# MCU.net
KiCad netlist of a schematic drawn in Altium Designer
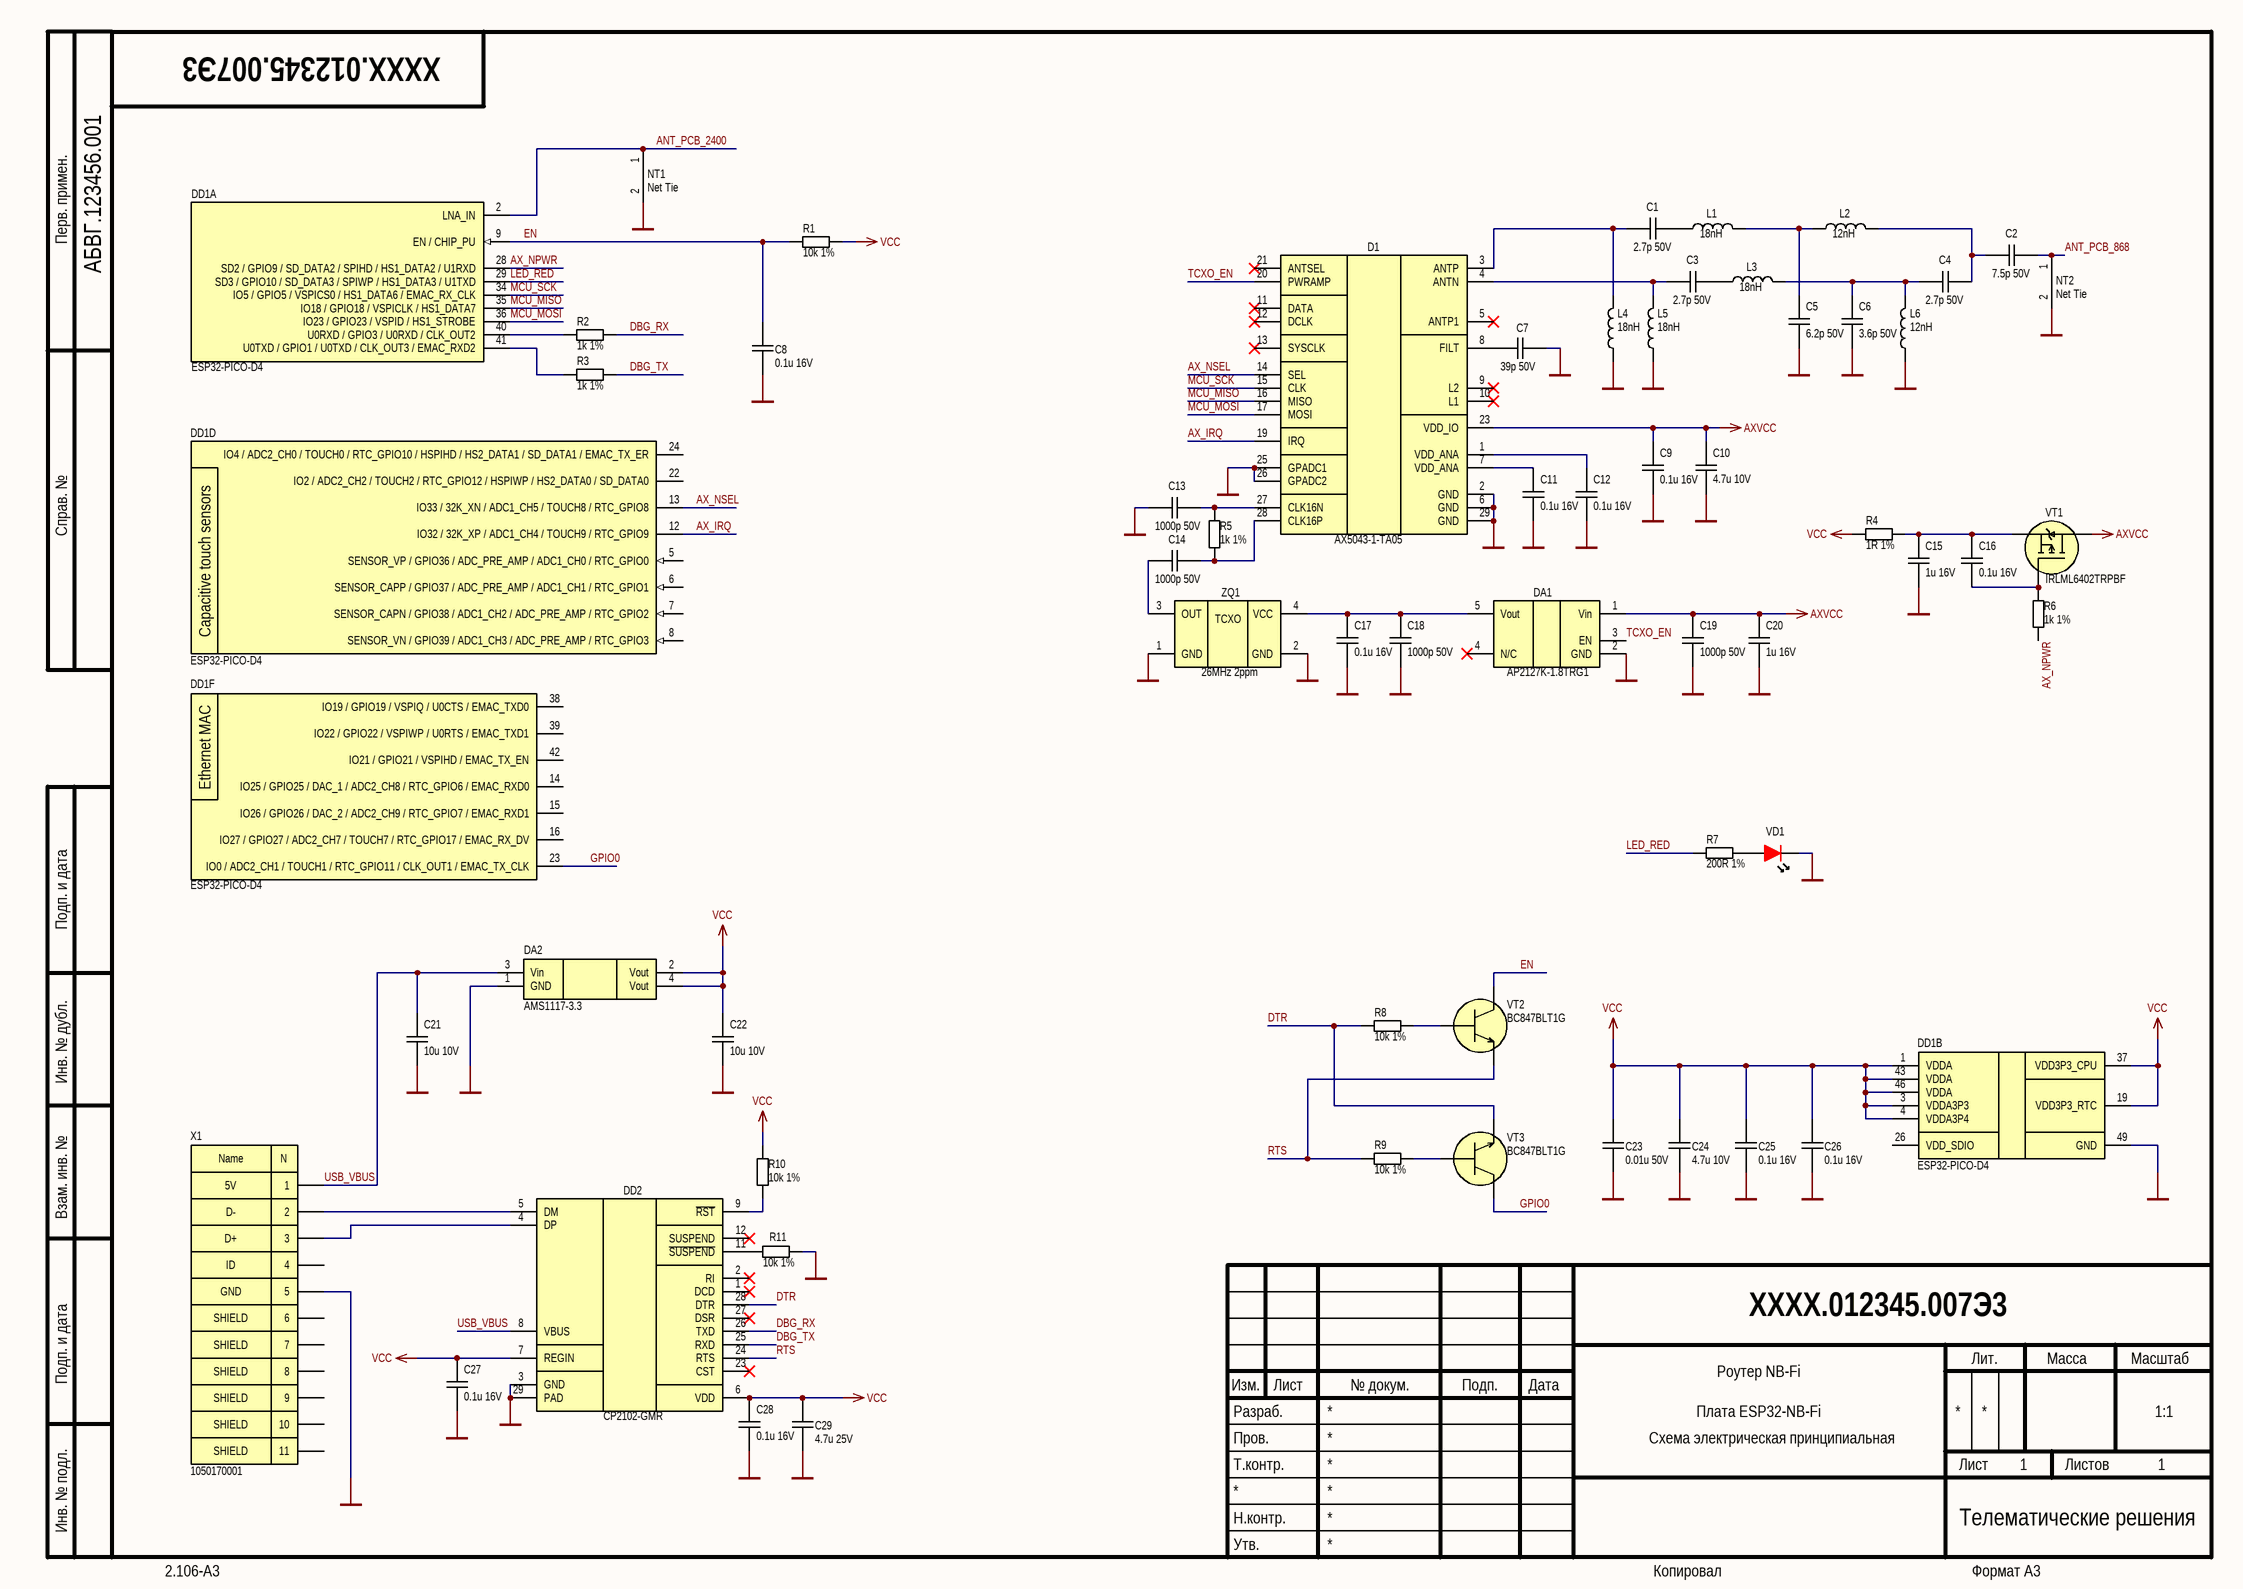
[diagram p0: MCU.SchDoc]

(export (version "E")
  (design (tool "Eeschema 10.0.6"))
  (components
    (comp (ref "C1")
      (value "2.7p 50V")
      (footprint "C0603")
      (description "CERCAP 2.7p/50V 0603 BNPO")
      (fields (field (name "PARTNUMBER") "CC0603BRNPO9BN2R7"))
      (libsource (lib "Capacitors") (part "CC0603BRNPO9BN2R7"))
    )
    (comp (ref "C2")
      (value "7.5p 50V")
      (footprint "C0603")
      (description "CERCAP 7.5p/50V 0603 BNPO")
      (fields (field (name "PARTNUMBER") "CC0603BRNPO9BN7R5"))
      (libsource (lib "Capacitors") (part "CC0603BRNPO9BN7R5"))
    )
    (comp (ref "C3")
      (value "2.7p 50V")
      (footprint "C0603")
      (description "CERCAP 2.7p/50V 0603 BNPO")
      (fields (field (name "PARTNUMBER") "CC0603BRNPO9BN2R7"))
      (libsource (lib "Capacitors") (part "CC0603BRNPO9BN2R7"))
    )
    (comp (ref "C4")
      (value "2.7p 50V")
      (footprint "C0603")
      (description "CERCAP 2.7p/50V 0603 BNPO")
      (fields (field (name "PARTNUMBER") "CC0603BRNPO9BN2R7"))
      (libsource (lib "Capacitors") (part "CC0603BRNPO9BN2R7"))
    )
    (comp (ref "C5")
      (value "6.2p 50V")
      (footprint "C0603")
      (description "CERCAP 6.2p/50V 0603 BNPO")
      (fields (field (name "PARTNUMBER") "CC0603BRNPO9BN6R2"))
      (libsource (lib "Capacitors") (part "CC0603BRNPO9BN6R2"))
    )
    (comp (ref "C6")
      (value "3.6p 50V")
      (footprint "C0603")
      (description "CERCAP 3.6p/50V 0603 BNPO")
      (fields (field (name "PARTNUMBER") "CC0603BRNPO9BN3R6"))
      (libsource (lib "Capacitors") (part "CC0603BRNPO9BN3R6"))
    )
    (comp (ref "C7")
      (value "39p 50V")
      (footprint "C0603")
      (description "CERCAP 39p/50V 0603 JNPO")
      (fields (field (name "PARTNUMBER") "CC0603JRNPO9BN390"))
      (libsource (lib "Capacitors") (part "CC0603JRNPO9BN390"))
    )
    (comp (ref "C8")
      (value "0.1u 16V")
      (footprint "C0603")
      (description "CERCAP 0.1/16V 0603 KX7R")
      (fields (field (name "PARTNUMBER") "CC0603KRX7R7BB104"))
      (libsource (lib "Capacitors") (part "CC0603KRX7R7BB104"))
    )
    (comp (ref "C9")
      (value "0.1u 16V")
      (footprint "C0603")
      (description "CERCAP 0.1/16V 0603 KX7R")
      (fields (field (name "PARTNUMBER") "CC0603KRX7R7BB104"))
      (libsource (lib "Capacitors") (part "CC0603KRX7R7BB104"))
    )
    (comp (ref "C10")
      (value "4.7u 10V")
      (footprint "C0603")
      (description "CERCAP 4.7/10V 0603 KX5R")
      (fields (field (name "PARTNUMBER") "CC0603KRX5R6BB475"))
      (libsource (lib "Passive") (part "C"))
    )
    (comp (ref "C11")
      (value "0.1u 16V")
      (footprint "C0603")
      (description "CERCAP 0.1/16V 0603 KX7R")
      (fields (field (name "PARTNUMBER") "CC0603KRX7R7BB104"))
      (libsource (lib "Capacitors") (part "CC0603KRX7R7BB104"))
    )
    (comp (ref "C12")
      (value "0.1u 16V")
      (footprint "C0603")
      (description "CERCAP 0.1/16V 0603 KX7R")
      (fields (field (name "PARTNUMBER") "CC0603KRX7R7BB104"))
      (libsource (lib "Capacitors") (part "CC0603KRX7R7BB104"))
    )
    (comp (ref "C13")
      (value "1000p 50V")
      (footprint "C0603")
      (description "CERCAP 1000p/50V 0603 JNPO")
      (fields (field (name "PARTNUMBER") "CC0603JRNPO9BN102"))
      (libsource (lib "Capacitors") (part "CC0603JRNPO9BN102"))
    )
    (comp (ref "C14")
      (value "1000p 50V")
      (footprint "C0603")
      (description "CERCAP 1000p/50V 0603 JNPO")
      (fields (field (name "PARTNUMBER") "CC0603JRNPO9BN102"))
      (libsource (lib "Capacitors") (part "CC0603JRNPO9BN102"))
    )
    (comp (ref "C15")
      (value "1u 16V")
      (footprint "C0603")
      (description "CERCAP 1/16V 0603 KX7R")
      (fields (field (name "PARTNUMBER") "CC0603KRX7R7BB105"))
      (libsource (lib "Capacitors") (part "CC0603KRX7R7BB105"))
    )
    (comp (ref "C16")
      (value "0.1u 16V")
      (footprint "C0603")
      (description "CERCAP 0.1/16V 0603 KX7R")
      (fields (field (name "PARTNUMBER") "CC0603KRX7R7BB104"))
      (libsource (lib "Capacitors") (part "CC0603KRX7R7BB104"))
    )
    (comp (ref "C17")
      (value "0.1u 16V")
      (footprint "C0603")
      (description "CERCAP 0.1/16V 0603 KX7R")
      (fields (field (name "PARTNUMBER") "CC0603KRX7R7BB104"))
      (libsource (lib "Capacitors") (part "CC0603KRX7R7BB104"))
    )
    (comp (ref "C18")
      (value "1000p 50V")
      (footprint "C0603")
      (description "CERCAP 1000p/50V 0603 JNPO")
      (fields (field (name "PARTNUMBER") "CC0603JRNPO9BN102"))
      (libsource (lib "Capacitors") (part "CC0603JRNPO9BN102"))
    )
    (comp (ref "C19")
      (value "1000p 50V")
      (footprint "C0603")
      (description "CERCAP 1000p/50V 0603 JNPO")
      (fields (field (name "PARTNUMBER") "CC0603JRNPO9BN102"))
      (libsource (lib "Capacitors") (part "CC0603JRNPO9BN102"))
    )
    (comp (ref "C20")
      (value "1u 16V")
      (footprint "C0603")
      (description "CERCAP 1/16V 0603 KX7R")
      (fields (field (name "PARTNUMBER") "CC0603KRX7R7BB105"))
      (libsource (lib "Capacitors") (part "CC0603KRX7R7BB105"))
    )
    (comp (ref "C21")
      (value "10u 10V")
      (footprint "C0805")
      (description "10µF ±10% 10V Ceramic Capacitor X5R 0805 (2012 Metric)")
      (fields (field (name "PARTNUMBER") "CL21A106KPFNNNG"))
      (libsource (lib "Capacitors") (part "CL21A106KPFNNNG"))
    )
    (comp (ref "C22")
      (value "10u 10V")
      (footprint "C0805")
      (description "10µF ±10% 10V Ceramic Capacitor X5R 0805 (2012 Metric)")
      (fields (field (name "PARTNUMBER") "CL21A106KPFNNNG"))
      (libsource (lib "Capacitors") (part "CL21A106KPFNNNG"))
    )
    (comp (ref "C23")
      (value "0.01u 50V")
      (footprint "C0603")
      (description "CAP CER 10000PF 50V X7R 0603")
      (fields (field (name "PARTNUMBER") "CC0603KRX7R9BB103"))
      (libsource (lib "Capacitors") (part "CC0603KRX7R9BB103"))
    )
    (comp (ref "C24")
      (value "4.7u 10V")
      (footprint "C0603")
      (description "CERCAP 4.7/10V 0603 KX5R")
      (fields (field (name "PARTNUMBER") "CC0603KRX5R6BB475"))
      (libsource (lib "Passive") (part "C"))
    )
    (comp (ref "C25")
      (value "0.1u 16V")
      (footprint "C0603")
      (description "CERCAP 0.1/16V 0603 KX7R")
      (fields (field (name "PARTNUMBER") "CC0603KRX7R7BB104"))
      (libsource (lib "Capacitors") (part "CC0603KRX7R7BB104"))
    )
    (comp (ref "C26")
      (value "0.1u 16V")
      (footprint "C0603")
      (description "CERCAP 0.1/16V 0603 KX7R")
      (fields (field (name "PARTNUMBER") "CC0603KRX7R7BB104"))
      (libsource (lib "Capacitors") (part "CC0603KRX7R7BB104"))
    )
    (comp (ref "C27")
      (value "0.1u 16V")
      (footprint "C0603")
      (description "CERCAP 0.1/16V 0603 KX7R")
      (fields (field (name "PARTNUMBER") "CC0603KRX7R7BB104"))
      (libsource (lib "Capacitors") (part "CC0603KRX7R7BB104"))
    )
    (comp (ref "C28")
      (value "0.1u 16V")
      (footprint "C0603")
      (description "CERCAP 0.1/16V 0603 KX7R")
      (fields (field (name "PARTNUMBER") "CC0603KRX7R7BB104"))
      (libsource (lib "Capacitors") (part "CC0603KRX7R7BB104"))
    )
    (comp (ref "C29")
      (value "4.7u 25V")
      (footprint "C0805")
      (description "4.7µF ±10% 25V Ceramic Capacitor X5R 0805 (2012 Metric)")
      (fields (field (name "PARTNUMBER") "CL21A475KAQNNNE"))
      (libsource (lib "Capacitors") (part "CL21A475KAQNNNE"))
    )
    (comp (ref "D1")
      (value "AX5043-1-TA05")
      (footprint "QFN28")
      (description "RF Transceiver RADIO TRANSCEIVER")
      (libsource (lib "Integrated Circuits (ICs)") (part "AX5043-1-TA05"))
    )
    (comp (ref "DA1")
      (value "AP2127K-1.8TRG1")
      (footprint "SOT23-5")
      (description "LDO Voltage Regulators 1.8V 80mA CMOS LDO w/Enable")
      (libsource (lib "Integrated Circuits (ICs)") (part "AP2127K-1.8TRG1"))
    )
    (comp (ref "DA2")
      (value "AMS1117-3.3")
      (footprint "SOT223-4")
      (description "1A LOW DROPOUT VOLTAGE REGULATOR")
      (libsource (lib "Integrated Circuits (ICs)") (part "AMS1117-3.3"))
    )
    (comp (ref "DD1")
      (value "ESP32-PICO-D4")
      (footprint "QFN48-7x7")
      (libsource (lib "Integrated Circuits (ICs)") (part "ESP32-PICO-D4"))
    )
    (comp (ref "DD2")
      (value "CP2102-GMR")
      (footprint "QFN28")
      (description "IC USB-TO-UART BRIDGE 28VQFN")
      (libsource (lib "Integrated Circuits (ICs)") (part "CP2102-GMR"))
    )
    (comp (ref "L1")
      (value "18nH")
      (footprint "L0603_LQW")
      (description "Fixed Inductors 0603 18nH 2%")
      (fields (field (name "PARTNUMBER") "LQW18AN18NG00D"))
      (libsource (lib "Inductors") (part "LQW18AN18NG00D"))
    )
    (comp (ref "L2")
      (value "12nH")
      (footprint "L0603_LQW")
      (description "Fixed Inductors 12 NH 5% (R)")
      (fields (field (name "PARTNUMBER") "LQW18AN12NJ00D"))
      (libsource (lib "Inductors") (part "LQW18AN12NJ00D"))
    )
    (comp (ref "L3")
      (value "18nH")
      (footprint "L0603_LQW")
      (description "Fixed Inductors 0603 18nH 2%")
      (fields (field (name "PARTNUMBER") "LQW18AN18NG00D"))
      (libsource (lib "Inductors") (part "LQW18AN18NG00D"))
    )
    (comp (ref "L4")
      (value "18nH")
      (footprint "L0603_LQW")
      (description "Fixed Inductors 0603 18nH 2%")
      (fields (field (name "PARTNUMBER") "LQW18AN18NG00D"))
      (libsource (lib "Inductors") (part "LQW18AN18NG00D"))
    )
    (comp (ref "L5")
      (value "18nH")
      (footprint "L0603_LQW")
      (description "Fixed Inductors 0603 18nH 2%")
      (fields (field (name "PARTNUMBER") "LQW18AN18NG00D"))
      (libsource (lib "Inductors") (part "LQW18AN18NG00D"))
    )
    (comp (ref "L6")
      (value "12nH")
      (description "Fixed Inductors 12 NH 5% (R)")
      (fields (field (name "PARTNUMBER") "LQW18AN12NJ00D"))
      (libsource (lib "Inductors") (part "LQW18AN12NJ00D"))
    )
    (comp (ref "NT1")
      (value "Net Tie")
      (footprint "NETTIE-5.0x2.0")
      (description "PCB Net Tie")
      (libsource (lib "Special") (part "NT-1"))
    )
    (comp (ref "NT2")
      (value "Net Tie")
      (footprint "NETTIE-5.0x2.0")
      (description "PCB Net Tie")
      (libsource (lib "Special") (part "NT-1"))
    )
    (comp (ref "R1")
      (value "10k 1%")
      (footprint "R0603")
      (description "RES 0603 10K 1%")
      (fields (field (name "PARTNUMBER") "RC0603FR-0710KL"))
      (libsource (lib "") (part "RC0603FR-0710KL_1"))
    )
    (comp (ref "R2")
      (value "1k 1%")
      (footprint "R0603")
      (description "RES 0603 1K 1%")
      (fields (field (name "PARTNUMBER") "RC0603FR-071KL"))
      (libsource (lib "Resistors") (part "RC0603FR-071KL"))
    )
    (comp (ref "R3")
      (value "1k 1%")
      (footprint "R0603")
      (description "RES 0603 1K 1%")
      (fields (field (name "PARTNUMBER") "RC0603FR-071KL"))
      (libsource (lib "Resistors") (part "RC0603FR-071KL"))
    )
    (comp (ref "R4")
      (value "1R 1%")
      (footprint "R0603")
      (description "RES 0603 1R 1%")
      (fields (field (name "PARTNUMBER") "RC0603FR-071RL"))
      (libsource (lib "Passive") (part "R"))
    )
    (comp (ref "R5")
      (value "1k 1%")
      (footprint "R0603")
      (description "RES 0603 1K 1%")
      (fields (field (name "PARTNUMBER") "RC0603FR-071KL"))
      (libsource (lib "Resistors") (part "RC0603FR-071KL"))
    )
    (comp (ref "R6")
      (value "1k 1%")
      (footprint "R0603")
      (description "RES 0603 1K 1%")
      (fields (field (name "PARTNUMBER") "RC0603FR-071KL"))
      (libsource (lib "Resistors") (part "RC0603FR-071KL"))
    )
    (comp (ref "R7")
      (value "200R 1%")
      (footprint "R0603")
      (description "RES 0603 200R 1%")
      (fields (field (name "PARTNUMBER") "RC0603FR-07200RL"))
      (libsource (lib "Resistors") (part "RC0603FR-07200RL"))
    )
    (comp (ref "R8")
      (value "10k 1%")
      (footprint "R0603")
      (description "RES 0603 10K 1%")
      (fields (field (name "PARTNUMBER") "RC0603FR-0710KL"))
      (libsource (lib "") (part "RC0603FR-0710KL_1"))
    )
    (comp (ref "R9")
      (value "10k 1%")
      (footprint "R0603")
      (description "RES 0603 10K 1%")
      (fields (field (name "PARTNUMBER") "RC0603FR-0710KL"))
      (libsource (lib "") (part "RC0603FR-0710KL_1"))
    )
    (comp (ref "R10")
      (value "10k 1%")
      (footprint "R0603")
      (description "RES 0603 10K 1%")
      (fields (field (name "PARTNUMBER") "RC0603FR-0710KL"))
      (libsource (lib "Resistors") (part "RC0603FR-0710KL"))
    )
    (comp (ref "R11")
      (value "10k 1%")
      (footprint "R0603")
      (description "RES 0603 10K 1%")
      (fields (field (name "PARTNUMBER") "RC0603FR-0710KL"))
      (libsource (lib "") (part "RC0603FR-0710KL_2"))
    )
    (comp (ref "VD1")
      (value "RED")
      (footprint "LED0603_RED")
      (description "LED Red 0603")
      (fields (field (name "PARTNUMBER") "FYLS-0603URC"))
      (libsource (lib "Diodes") (part "FYLS-0603URC"))
    )
    (comp (ref "VT1")
      (value "IRLML6402TRPBF")
      (footprint "SOT23-3L")
      (description "MOSFET MOSFT P-Ch -3.7A 65mOhm 8nC Log Lvl")
      (libsource (lib "Discrete Semiconductor Products") (part "IRLML6402TRPBF"))
    )
    (comp (ref "VT2")
      (value "BC847BLT1G")
      (footprint "SOT23-3L")
      (description "Bipolar (BJT) Transistor NPN 45V 100mA 100MHz 300mW Surface Mount SOT-23-3 (TO-236)")
      (libsource (lib "Discrete Semiconductor Products") (part "BC847BLT1G"))
    )
    (comp (ref "VT3")
      (value "BC847BLT1G")
      (footprint "SOT23-3L")
      (description "Bipolar (BJT) Transistor NPN 45V 100mA 100MHz 300mW Surface Mount SOT-23-3 (TO-236)")
      (libsource (lib "Discrete Semiconductor Products") (part "BC847BLT1G"))
    )
    (comp (ref "X1")
      (value "1050170001")
      (footprint "1050170001")
      (description "USB - micro B USB 2.0 Receptacle Connector 5 Position Surface Mount, Right Angle; Through Hole")
      (libsource (lib "Connectors") (part "1050170001"))
    )
    (comp (ref "ZQ1")
      (value "26MHz 2ppm")
      (footprint "QSMD2.0x1.6x0.7")
      (description "TCXO Oscillator 4-pin")
      (fields (field (name "PARTNUMBER") "NT2016SA-26.000000MHZ-NBG2"))
      (libsource (lib "Crystals, Oscillators, Resonators") (part "NT2016SA-26.000000MHZ-NBG2"))
    )
  )
  (nets
    (net (code "1") (name "/ANT_PCB_868") (class "Default")
      (node (ref "C2") (pin "2") (pinfunction "2_2") (pintype "passive"))
      (node (ref "NT2") (pin "1") (pinfunction "1_1") (pintype "passive"))
    )
    (net (code "2") (name "/ANT_PCB_2400") (class "Default")
      (node (ref "DD1") (pin "2") (pinfunction "LNA_IN_2") (pintype "passive"))
      (node (ref "NT1") (pin "1") (pinfunction "1_1") (pintype "passive"))
    )
    (net (code "3") (name "/AX_IRQ") (class "Default")
      (node (ref "D1") (pin "19") (pinfunction "IRQ_19") (pintype "passive"))
      (node (ref "DD1") (pin "12") (pinfunction "IO32_/_32K_XP_/_ADC1_CH4_/_TOUCH9_/_RTC_GPIO9_12") (pintype "passive"))
    )
    (net (code "4") (name "/AX_NPWR") (class "Default")
      (node (ref "DD1") (pin "28") (pinfunction "SD2_/_GPIO9_/_SD_DATA2_/_SPIHD_/_HS1_DATA2_/_U1RXD_28") (pintype "passive"))
      (node (ref "R6") (pin "1") (pinfunction "1_1") (pintype "passive"))
    )
    (net (code "5") (name "/AX_NSEL") (class "Default")
      (node (ref "D1") (pin "14") (pinfunction "SEL_14") (pintype "passive"))
      (node (ref "DD1") (pin "13") (pinfunction "IO33_/_32K_XN_/_ADC1_CH5_/_TOUCH8_/_RTC_GPIO8_13") (pintype "passive"))
    )
    (net (code "6") (name "/DBG_RX") (class "Default")
      (node (ref "DD2") (pin "26") (pinfunction "TXD_26") (pintype "passive"))
      (node (ref "R2") (pin "2") (pinfunction "2_2") (pintype "passive"))
    )
    (net (code "7") (name "/DBG_TX") (class "Default")
      (node (ref "DD2") (pin "25") (pinfunction "RXD_25") (pintype "passive"))
      (node (ref "R3") (pin "2") (pinfunction "2_2") (pintype "passive"))
    )
    (net (code "8") (name "/DTR") (class "Default")
      (node (ref "DD2") (pin "28") (pinfunction "DTR_28") (pintype "passive"))
      (node (ref "R8") (pin "1") (pinfunction "1_1") (pintype "passive"))
      (node (ref "VT3") (pin "2") (pinfunction "E_2") (pintype "passive"))
    )
    (net (code "9") (name "/EN") (class "Default")
      (node (ref "C8") (pin "2") (pinfunction "2_2") (pintype "passive"))
      (node (ref "DD1") (pin "9") (pinfunction "EN_/_CHIP_PU_9") (pintype "input"))
      (node (ref "R1") (pin "1") (pinfunction "1_1") (pintype "passive"))
      (node (ref "VT2") (pin "3") (pinfunction "C_3") (pintype "passive"))
    )
    (net (code "10") (name "/GPIO0") (class "Default")
      (node (ref "DD1") (pin "23") (pinfunction "IO0_/_ADC2_CH1_/_TOUCH1_/_RTC_GPIO11_/_CLK_OUT1_/_EMAC_TX_CLK_23") (pintype "passive"))
      (node (ref "VT3") (pin "3") (pinfunction "C_3") (pintype "passive"))
    )
    (net (code "11") (name "/LED_RED") (class "Default")
      (node (ref "DD1") (pin "29") (pinfunction "SD3_/_GPIO10_/_SD_DATA3_/_SPIWP_/_HS1_DATA3_/_U1TXD_29") (pintype "open_collector"))
      (node (ref "R7") (pin "1") (pinfunction "1_1") (pintype "passive"))
    )
    (net (code "12") (name "/MCU_MISO") (class "Default")
      (node (ref "D1") (pin "16") (pinfunction "MISO_16") (pintype "passive"))
      (node (ref "DD1") (pin "35") (pinfunction "IO18_/_GPIO18_/_VSPICLK_/_HS1_DATA7_35") (pintype "open_collector"))
    )
    (net (code "13") (name "/MCU_MOSI") (class "Default")
      (node (ref "D1") (pin "17") (pinfunction "MOSI_17") (pintype "passive"))
      (node (ref "DD1") (pin "36") (pinfunction "IO23_/_GPIO23_/_VSPID_/_HS1_STROBE_36") (pintype "passive"))
    )
    (net (code "14") (name "/MCU_SCK") (class "Default")
      (node (ref "D1") (pin "15") (pinfunction "CLK_15") (pintype "passive"))
      (node (ref "DD1") (pin "34") (pinfunction "IO5_/_GPIO5_/_VSPICS0_/_HS1_DATA6_/_EMAC_RX_CLK_34") (pintype "passive"))
    )
    (net (code "15") (name "/RTS") (class "Default")
      (node (ref "DD2") (pin "24") (pinfunction "RTS_24") (pintype "passive"))
      (node (ref "R9") (pin "1") (pinfunction "1_1") (pintype "passive"))
      (node (ref "VT2") (pin "2") (pinfunction "E_2") (pintype "passive"))
    )
    (net (code "16") (name "/TCXO_EN") (class "Default")
      (node (ref "D1") (pin "20") (pinfunction "PWRAMP_20") (pintype "passive"))
      (node (ref "DA1") (pin "3") (pinfunction "EN_3") (pintype "passive"))
    )
    (net (code "17") (name "/USB_VBUS") (class "Default")
      (node (ref "C21") (pin "2") (pinfunction "2_2") (pintype "passive"))
      (node (ref "DA2") (pin "3") (pinfunction "Vin_3") (pintype "passive"))
      (node (ref "DD2") (pin "8") (pinfunction "VBUS_8") (pintype "passive"))
      (node (ref "X1") (pin "1") (pinfunction "1_1") (pintype "passive"))
    )
    (net (code "18") (name "AXVCC") (class "Default")
      (node (ref "C10") (pin "2") (pinfunction "2_2") (pintype "passive"))
      (node (ref "C19") (pin "1") (pinfunction "1_1") (pintype "passive"))
      (node (ref "C20") (pin "2") (pinfunction "2_2") (pintype "passive"))
      (node (ref "C9") (pin "2") (pinfunction "2_2") (pintype "passive"))
      (node (ref "D1") (pin "23") (pinfunction "VDD_IO_23") (pintype "passive"))
      (node (ref "DA1") (pin "1") (pinfunction "Vin_1") (pintype "passive"))
      (node (ref "VT1") (pin "3") (pinfunction "D_3") (pintype "passive"))
    )
    (net (code "19") (name "GND") (class "Default")
      (node (ref "C10") (pin "1") (pinfunction "1_1") (pintype "passive"))
      (node (ref "C11") (pin "1") (pinfunction "1_1") (pintype "passive"))
      (node (ref "C12") (pin "1") (pinfunction "1_1") (pintype "passive"))
      (node (ref "C13") (pin "2") (pinfunction "2_2") (pintype "passive"))
      (node (ref "C15") (pin "1") (pinfunction "1_1") (pintype "passive"))
      (node (ref "C17") (pin "1") (pinfunction "1_1") (pintype "passive"))
      (node (ref "C18") (pin "2") (pinfunction "2_2") (pintype "passive"))
      (node (ref "C19") (pin "2") (pinfunction "2_2") (pintype "passive"))
      (node (ref "C20") (pin "1") (pinfunction "1_1") (pintype "passive"))
      (node (ref "C21") (pin "1") (pinfunction "1_1") (pintype "passive"))
      (node (ref "C22") (pin "1") (pinfunction "1_1") (pintype "passive"))
      (node (ref "C23") (pin "1") (pinfunction "1_1") (pintype "passive"))
      (node (ref "C24") (pin "1") (pinfunction "1_1") (pintype "passive"))
      (node (ref "C25") (pin "1") (pinfunction "1_1") (pintype "passive"))
      (node (ref "C26") (pin "1") (pinfunction "1_1") (pintype "passive"))
      (node (ref "C27") (pin "1") (pinfunction "1_1") (pintype "passive"))
      (node (ref "C28") (pin "1") (pinfunction "1_1") (pintype "passive"))
      (node (ref "C29") (pin "1") (pinfunction "1_1") (pintype "passive"))
      (node (ref "C5") (pin "1") (pinfunction "1_1") (pintype "passive"))
      (node (ref "C6") (pin "1") (pinfunction "1_1") (pintype "passive"))
      (node (ref "C7") (pin "2") (pinfunction "2_2") (pintype "passive"))
      (node (ref "C8") (pin "1") (pinfunction "1_1") (pintype "passive"))
      (node (ref "C9") (pin "1") (pinfunction "1_1") (pintype "passive"))
      (node (ref "D1") (pin "2") (pinfunction "GND_2") (pintype "passive"))
      (node (ref "D1") (pin "25") (pinfunction "GPADC1_25") (pintype "passive"))
      (node (ref "D1") (pin "26") (pinfunction "GPADC2_26") (pintype "passive"))
      (node (ref "D1") (pin "29") (pinfunction "GND_29") (pintype "passive"))
      (node (ref "D1") (pin "6") (pinfunction "GND_6") (pintype "passive"))
      (node (ref "DA1") (pin "2") (pinfunction "GND_2") (pintype "passive"))
      (node (ref "DA2") (pin "1") (pinfunction "GND_1") (pintype "passive"))
      (node (ref "DD1") (pin "49") (pinfunction "GND_49") (pintype "power_in"))
      (node (ref "DD2") (pin "29") (pinfunction "PAD_29") (pintype "passive"))
      (node (ref "DD2") (pin "3") (pinfunction "GND_3") (pintype "passive"))
      (node (ref "L4") (pin "1") (pinfunction "1_1") (pintype "passive"))
      (node (ref "L5") (pin "1") (pinfunction "1_1") (pintype "passive"))
      (node (ref "L6") (pin "1") (pinfunction "1_1") (pintype "passive"))
      (node (ref "NT1") (pin "2") (pinfunction "2_2") (pintype "passive"))
      (node (ref "NT2") (pin "2") (pinfunction "2_2") (pintype "passive"))
      (node (ref "R11") (pin "1") (pinfunction "1_1") (pintype "passive"))
      (node (ref "VD1") (pin "2") (pinfunction "2_2") (pintype "passive"))
      (node (ref "X1") (pin "5") (pinfunction "5_5") (pintype "passive"))
      (node (ref "ZQ1") (pin "1") (pinfunction "GND_1") (pintype "passive"))
      (node (ref "ZQ1") (pin "2") (pinfunction "GND_2") (pintype "passive"))
    )
    (net (code "20") (name "Net-(C1-Pad2)") (class "Default")
      (node (ref "C1") (pin "2") (pinfunction "2_2") (pintype "passive"))
      (node (ref "L1") (pin "1") (pinfunction "1_1") (pintype "passive"))
    )
    (net (code "21") (name "Net-(C2-Pad1)") (class "Default")
      (node (ref "C2") (pin "1") (pinfunction "1_1") (pintype "passive"))
      (node (ref "C4") (pin "2") (pinfunction "2_2") (pintype "passive"))
      (node (ref "L2") (pin "2") (pinfunction "2_2") (pintype "passive"))
    )
    (net (code "22") (name "Net-(C3-Pad2)") (class "Default")
      (node (ref "C3") (pin "2") (pinfunction "2_2") (pintype "passive"))
      (node (ref "L3") (pin "1") (pinfunction "1_1") (pintype "passive"))
    )
    (net (code "23") (name "Net-(C4-Pad1)") (class "Default")
      (node (ref "C4") (pin "1") (pinfunction "1_1") (pintype "passive"))
      (node (ref "C6") (pin "2") (pinfunction "2_2") (pintype "passive"))
      (node (ref "L3") (pin "2") (pinfunction "2_2") (pintype "passive"))
      (node (ref "L6") (pin "2") (pinfunction "2_2") (pintype "passive"))
    )
    (net (code "24") (name "Net-(C5-Pad2)") (class "Default")
      (node (ref "C5") (pin "2") (pinfunction "2_2") (pintype "passive"))
      (node (ref "L1") (pin "2") (pinfunction "2_2") (pintype "passive"))
      (node (ref "L2") (pin "1") (pinfunction "1_1") (pintype "passive"))
    )
    (net (code "25") (name "Net-(C11-Pad2)") (class "Default")
      (node (ref "C11") (pin "2") (pinfunction "2_2") (pintype "passive"))
      (node (ref "D1") (pin "7") (pinfunction "VDD_ANA_7") (pintype "passive"))
    )
    (net (code "26") (name "Net-(C12-Pad2)") (class "Default")
      (node (ref "C12") (pin "2") (pinfunction "2_2") (pintype "passive"))
      (node (ref "D1") (pin "1") (pinfunction "VDD_ANA_1") (pintype "passive"))
    )
    (net (code "27") (name "Net-(D1-ANTN)") (class "Default")
      (node (ref "C3") (pin "1") (pinfunction "1_1") (pintype "passive"))
      (node (ref "D1") (pin "4") (pinfunction "ANTN_4") (pintype "passive"))
      (node (ref "L5") (pin "2") (pinfunction "2_2") (pintype "passive"))
    )
    (net (code "28") (name "Net-(D1-ANTP)") (class "Default")
      (node (ref "C1") (pin "1") (pinfunction "1_1") (pintype "passive"))
      (node (ref "D1") (pin "3") (pinfunction "ANTP_3") (pintype "passive"))
      (node (ref "L4") (pin "2") (pinfunction "2_2") (pintype "passive"))
    )
    (net (code "29") (name "Net-(D1-CLK16N)") (class "Default")
      (node (ref "C13") (pin "1") (pinfunction "1_1") (pintype "passive"))
      (node (ref "D1") (pin "27") (pinfunction "CLK16N_27") (pintype "passive"))
      (node (ref "R5") (pin "2") (pinfunction "2_2") (pintype "passive"))
    )
    (net (code "30") (name "Net-(D1-CLK16P)") (class "Default")
      (node (ref "C14") (pin "1") (pinfunction "1_1") (pintype "passive"))
      (node (ref "D1") (pin "28") (pinfunction "CLK16P_28") (pintype "passive"))
      (node (ref "R5") (pin "1") (pinfunction "1_1") (pintype "passive"))
    )
    (net (code "31") (name "Net-(D1-FILT)") (class "Default")
      (node (ref "C7") (pin "1") (pinfunction "1_1") (pintype "passive"))
      (node (ref "D1") (pin "8") (pinfunction "FILT_8") (pintype "passive"))
    )
    (net (code "32") (name "Net-(DA1-Vout)") (class "Default")
      (node (ref "C17") (pin "2") (pinfunction "2_2") (pintype "passive"))
      (node (ref "C18") (pin "1") (pinfunction "1_1") (pintype "passive"))
      (node (ref "DA1") (pin "5") (pinfunction "Vout_5") (pintype "passive"))
      (node (ref "ZQ1") (pin "4") (pinfunction "VCC_4") (pintype "passive"))
    )
    (net (code "33") (name "Net-(DD1A-U0RXD_{slash}_GPIO3_{slash}_U0RXD_{slash}_CLK_OUT2)") (class "Default")
      (node (ref "DD1") (pin "40") (pinfunction "U0RXD_/_GPIO3_/_U0RXD_/_CLK_OUT2_40") (pintype "passive"))
      (node (ref "R2") (pin "1") (pinfunction "1_1") (pintype "passive"))
    )
    (net (code "34") (name "Net-(DD1A-U0TXD_{slash}_GPIO1_{slash}_U0TXD_{slash}_CLK_OUT3_{slash}_EMAC_RXD2)") (class "Default")
      (node (ref "DD1") (pin "41") (pinfunction "U0TXD_/_GPIO1_/_U0TXD_/_CLK_OUT3_/_EMAC_RXD2_41") (pintype "passive"))
      (node (ref "R3") (pin "1") (pinfunction "1_1") (pintype "passive"))
    )
    (net (code "35") (name "Net-(DD2-DM)") (class "Default")
      (node (ref "DD2") (pin "5") (pinfunction "DM_5") (pintype "passive"))
      (node (ref "X1") (pin "2") (pinfunction "2_2") (pintype "passive"))
    )
    (net (code "36") (name "Net-(DD2-DP)") (class "Default")
      (node (ref "DD2") (pin "4") (pinfunction "DP_4") (pintype "passive"))
      (node (ref "X1") (pin "3") (pinfunction "3_3") (pintype "passive"))
    )
    (net (code "37") (name "Net-(DD2-~{RST})") (class "Default")
      (node (ref "DD2") (pin "9") (pinfunction "~{RST}_9") (pintype "passive"))
      (node (ref "R10") (pin "1") (pinfunction "1_1") (pintype "passive"))
    )
    (net (code "38") (name "Net-(DD2-~{SUSPEND})") (class "Default")
      (node (ref "DD2") (pin "11") (pinfunction "~{SUSPEND}_11") (pintype "passive"))
      (node (ref "R11") (pin "2") (pinfunction "2_2") (pintype "passive"))
    )
    (net (code "39") (name "Net-(R7-Pad2)") (class "Default")
      (node (ref "R7") (pin "2") (pinfunction "2_2") (pintype "passive"))
      (node (ref "VD1") (pin "1") (pinfunction "1_1") (pintype "passive"))
    )
    (net (code "40") (name "Net-(VT1-G)") (class "Default")
      (node (ref "C16") (pin "1") (pinfunction "1_1") (pintype "passive"))
      (node (ref "R6") (pin "2") (pinfunction "2_2") (pintype "passive"))
      (node (ref "VT1") (pin "1") (pinfunction "G_1") (pintype "passive"))
    )
    (net (code "41") (name "Net-(VT1-S)") (class "Default")
      (node (ref "C15") (pin "2") (pinfunction "2_2") (pintype "passive"))
      (node (ref "C16") (pin "2") (pinfunction "2_2") (pintype "passive"))
      (node (ref "R4") (pin "2") (pinfunction "2_2") (pintype "passive"))
      (node (ref "VT1") (pin "2") (pinfunction "S_2") (pintype "passive"))
    )
    (net (code "42") (name "Net-(VT2-B)") (class "Default")
      (node (ref "R8") (pin "2") (pinfunction "2_2") (pintype "passive"))
      (node (ref "VT2") (pin "1") (pinfunction "B_1") (pintype "passive"))
    )
    (net (code "43") (name "Net-(VT3-B)") (class "Default")
      (node (ref "R9") (pin "2") (pinfunction "2_2") (pintype "passive"))
      (node (ref "VT3") (pin "1") (pinfunction "B_1") (pintype "passive"))
    )
    (net (code "44") (name "Net-(ZQ1-OUT)") (class "Default")
      (node (ref "C14") (pin "2") (pinfunction "2_2") (pintype "passive"))
      (node (ref "ZQ1") (pin "3") (pinfunction "OUT_3") (pintype "passive"))
    )
    (net (code "45") (name "VCC") (class "Default")
      (node (ref "C22") (pin "2") (pinfunction "2_2") (pintype "passive"))
      (node (ref "C23") (pin "2") (pinfunction "2_2") (pintype "passive"))
      (node (ref "C24") (pin "2") (pinfunction "2_2") (pintype "passive"))
      (node (ref "C25") (pin "2") (pinfunction "2_2") (pintype "passive"))
      (node (ref "C26") (pin "2") (pinfunction "2_2") (pintype "passive"))
      (node (ref "C27") (pin "2") (pinfunction "2_2") (pintype "passive"))
      (node (ref "C28") (pin "2") (pinfunction "2_2") (pintype "passive"))
      (node (ref "C29") (pin "2") (pinfunction "2_2") (pintype "passive"))
      (node (ref "DA2") (pin "2") (pinfunction "Vout_2") (pintype "passive"))
      (node (ref "DA2") (pin "4") (pinfunction "Vout_4") (pintype "passive"))
      (node (ref "DD1") (pin "1") (pinfunction "VDDA_1") (pintype "power_in"))
      (node (ref "DD1") (pin "19") (pinfunction "VDD3P3_RTC_19") (pintype "power_in"))
      (node (ref "DD1") (pin "3") (pinfunction "VDDA3P3_3") (pintype "power_in"))
      (node (ref "DD1") (pin "37") (pinfunction "VDD3P3_CPU_37") (pintype "power_in"))
      (node (ref "DD1") (pin "4") (pinfunction "VDDA3P4_4") (pintype "power_in"))
      (node (ref "DD1") (pin "43") (pinfunction "VDDA_43") (pintype "power_in"))
      (node (ref "DD1") (pin "46") (pinfunction "VDDA_46") (pintype "power_in"))
      (node (ref "DD2") (pin "6") (pinfunction "VDD_6") (pintype "passive"))
      (node (ref "DD2") (pin "7") (pinfunction "REGIN_7") (pintype "passive"))
      (node (ref "R1") (pin "2") (pinfunction "2_2") (pintype "passive"))
      (node (ref "R10") (pin "2") (pinfunction "2_2") (pintype "passive"))
      (node (ref "R4") (pin "1") (pinfunction "1_1") (pintype "passive"))
    )
    (net (code "46") (name "unconnected-(D1-ANTP1-Pad5)") (class "Default")
      (node (ref "D1") (pin "5") (pinfunction "ANTP1_5") (pintype "passive+no_connect"))
    )
    (net (code "47") (name "unconnected-(D1-ANTSEL-Pad21)") (class "Default")
      (node (ref "D1") (pin "21") (pinfunction "ANTSEL_21") (pintype "passive+no_connect"))
    )
    (net (code "48") (name "unconnected-(D1-DATA-Pad11)") (class "Default")
      (node (ref "D1") (pin "11") (pinfunction "DATA_11") (pintype "passive+no_connect"))
    )
    (net (code "49") (name "unconnected-(D1-DCLK-Pad12)") (class "Default")
      (node (ref "D1") (pin "12") (pinfunction "DCLK_12") (pintype "passive+no_connect"))
    )
    (net (code "50") (name "unconnected-(D1-L1-Pad10)") (class "Default")
      (node (ref "D1") (pin "10") (pinfunction "L1_10") (pintype "passive+no_connect"))
    )
    (net (code "51") (name "unconnected-(D1-L2-Pad9)") (class "Default")
      (node (ref "D1") (pin "9") (pinfunction "L2_9") (pintype "passive+no_connect"))
    )
    (net (code "52") (name "unconnected-(D1-SYSCLK-Pad13)") (class "Default")
      (node (ref "D1") (pin "13") (pinfunction "SYSCLK_13") (pintype "passive+no_connect"))
    )
    (net (code "53") (name "unconnected-(DA1-N{slash}C-Pad4)") (class "Default")
      (node (ref "DA1") (pin "4") (pinfunction "N/C_4") (pintype "passive+no_connect"))
    )
    (net (code "54") (name "unconnected-(DD1B-VDD_SDIO-Pad26)") (class "Default")
      (node (ref "DD1") (pin "26") (pinfunction "VDD_SDIO_26") (pintype "power_in"))
    )
    (net (code "55") (name "unconnected-(DD1D-IO2_{slash}_ADC2_CH2_{slash}_TOUCH2_{slash}_RTC_GPIO12_{slash}_HSPIWP_{slash}_HS2_DATA0_{slash}_SD_DATA0-Pad22)") (class "Default")
      (node (ref "DD1") (pin "22") (pinfunction "IO2_/_ADC2_CH2_/_TOUCH2_/_RTC_GPIO12_/_HSPIWP_/_HS2_DATA0_/_SD_DATA0_22") (pintype "open_collector"))
    )
    (net (code "56") (name "unconnected-(DD1D-IO4_{slash}_ADC2_CH0_{slash}_TOUCH0_{slash}_RTC_GPIO10_{slash}_HSPIHD_{slash}_HS2_DATA1_{slash}_SD_DATA1_{slash}_EMAC_TX_ER-Pad24)") (class "Default")
      (node (ref "DD1") (pin "24") (pinfunction "IO4_/_ADC2_CH0_/_TOUCH0_/_RTC_GPIO10_/_HSPIHD_/_HS2_DATA1_/_SD_DATA1_/_EMAC_TX_ER_24") (pintype "passive"))
    )
    (net (code "57") (name "unconnected-(DD1D-SENSOR_CAPN_{slash}_GPIO38_{slash}_ADC1_CH2_{slash}_ADC_PRE_AMP_{slash}_RTC_GPIO2-Pad7)") (class "Default")
      (node (ref "DD1") (pin "7") (pinfunction "SENSOR_CAPN_/_GPIO38_/_ADC1_CH2_/_ADC_PRE_AMP_/_RTC_GPIO2_7") (pintype "input"))
    )
    (net (code "58") (name "unconnected-(DD1D-SENSOR_CAPP_{slash}_GPIO37_{slash}_ADC_PRE_AMP_{slash}_ADC1_CH1_{slash}_RTC_GPIO1-Pad6)") (class "Default")
      (node (ref "DD1") (pin "6") (pinfunction "SENSOR_CAPP_/_GPIO37_/_ADC_PRE_AMP_/_ADC1_CH1_/_RTC_GPIO1_6") (pintype "input"))
    )
    (net (code "59") (name "unconnected-(DD1D-SENSOR_VN_{slash}_GPIO39_{slash}_ADC1_CH3_{slash}_ADC_PRE_AMP_{slash}_RTC_GPIO3-Pad8)") (class "Default")
      (node (ref "DD1") (pin "8") (pinfunction "SENSOR_VN_/_GPIO39_/_ADC1_CH3_/_ADC_PRE_AMP_/_RTC_GPIO3_8") (pintype "input"))
    )
    (net (code "60") (name "unconnected-(DD1D-SENSOR_VP_{slash}_GPIO36_{slash}_ADC_PRE_AMP_{slash}_ADC1_CH0_{slash}_RTC_GPIO0-Pad5)") (class "Default")
      (node (ref "DD1") (pin "5") (pinfunction "SENSOR_VP_/_GPIO36_/_ADC_PRE_AMP_/_ADC1_CH0_/_RTC_GPIO0_5") (pintype "input"))
    )
    (net (code "61") (name "unconnected-(DD1F-IO19_{slash}_GPIO19_{slash}_VSPIQ_{slash}_U0CTS_{slash}_EMAC_TXD0-Pad38)") (class "Default")
      (node (ref "DD1") (pin "38") (pinfunction "IO19_/_GPIO19_/_VSPIQ_/_U0CTS_/_EMAC_TXD0_38") (pintype "passive"))
    )
    (net (code "62") (name "unconnected-(DD1F-IO21_{slash}_GPIO21_{slash}_VSPIHD_{slash}_EMAC_TX_EN-Pad42)") (class "Default")
      (node (ref "DD1") (pin "42") (pinfunction "IO21_/_GPIO21_/_VSPIHD_/_EMAC_TX_EN_42") (pintype "passive"))
    )
    (net (code "63") (name "unconnected-(DD1F-IO22_{slash}_GPIO22_{slash}_VSPIWP_{slash}_U0RTS_{slash}_EMAC_TXD1-Pad39)") (class "Default")
      (node (ref "DD1") (pin "39") (pinfunction "IO22_/_GPIO22_/_VSPIWP_/_U0RTS_/_EMAC_TXD1_39") (pintype "passive"))
    )
    (net (code "64") (name "unconnected-(DD1F-IO25_{slash}_GPIO25_{slash}_DAC_1_{slash}_ADC2_CH8_{slash}_RTC_GPIO6_{slash}_EMAC_RXD0-Pad14)") (class "Default")
      (node (ref "DD1") (pin "14") (pinfunction "IO25_/_GPIO25_/_DAC_1_/_ADC2_CH8_/_RTC_GPIO6_/_EMAC_RXD0_14") (pintype "passive"))
    )
    (net (code "65") (name "unconnected-(DD1F-IO26_{slash}_GPIO26_{slash}_DAC_2_{slash}_ADC2_CH9_{slash}_RTC_GPIO7_{slash}_EMAC_RXD1-Pad15)") (class "Default")
      (node (ref "DD1") (pin "15") (pinfunction "IO26_/_GPIO26_/_DAC_2_/_ADC2_CH9_/_RTC_GPIO7_/_EMAC_RXD1_15") (pintype "passive"))
    )
    (net (code "66") (name "unconnected-(DD1F-IO27_{slash}_GPIO27_{slash}_ADC2_CH7_{slash}_TOUCH7_{slash}_RTC_GPIO17_{slash}_EMAC_RX_DV-Pad16)") (class "Default")
      (node (ref "DD1") (pin "16") (pinfunction "IO27_/_GPIO27_/_ADC2_CH7_/_TOUCH7_/_RTC_GPIO17_/_EMAC_RX_DV_16") (pintype "passive"))
    )
    (net (code "67") (name "unconnected-(DD2-CST-Pad23)") (class "Default")
      (node (ref "DD2") (pin "23") (pinfunction "CST_23") (pintype "passive+no_connect"))
    )
    (net (code "68") (name "unconnected-(DD2-DCD-Pad1)") (class "Default")
      (node (ref "DD2") (pin "1") (pinfunction "DCD_1") (pintype "passive+no_connect"))
    )
    (net (code "69") (name "unconnected-(DD2-DSR-Pad27)") (class "Default")
      (node (ref "DD2") (pin "27") (pinfunction "DSR_27") (pintype "passive+no_connect"))
    )
    (net (code "70") (name "unconnected-(DD2-RI-Pad2)") (class "Default")
      (node (ref "DD2") (pin "2") (pinfunction "RI_2") (pintype "passive+no_connect"))
    )
    (net (code "71") (name "unconnected-(DD2-SUSPEND-Pad12)") (class "Default")
      (node (ref "DD2") (pin "12") (pinfunction "SUSPEND_12") (pintype "passive+no_connect"))
    )
    (net (code "72") (name "unconnected-(X1-Pad4)") (class "Default")
      (node (ref "X1") (pin "4") (pinfunction "4_4") (pintype "passive"))
    )
    (net (code "73") (name "unconnected-(X1-Pad6)") (class "Default")
      (node (ref "X1") (pin "6") (pinfunction "6_6") (pintype "passive"))
    )
    (net (code "74") (name "unconnected-(X1-Pad7)") (class "Default")
      (node (ref "X1") (pin "7") (pinfunction "7_7") (pintype "passive"))
    )
    (net (code "75") (name "unconnected-(X1-Pad8)") (class "Default")
      (node (ref "X1") (pin "8") (pinfunction "8_8") (pintype "passive"))
    )
    (net (code "76") (name "unconnected-(X1-Pad9)") (class "Default")
      (node (ref "X1") (pin "9") (pinfunction "9_9") (pintype "passive"))
    )
    (net (code "77") (name "unconnected-(X1-Pad10)") (class "Default")
      (node (ref "X1") (pin "10") (pinfunction "10_10") (pintype "passive"))
    )
    (net (code "78") (name "unconnected-(X1-Pad11)") (class "Default")
      (node (ref "X1") (pin "11") (pinfunction "11_11") (pintype "passive"))
    )
  )
)
